# Config_Interfaces.net
KiCad netlist of a schematic drawn in Altium Designer
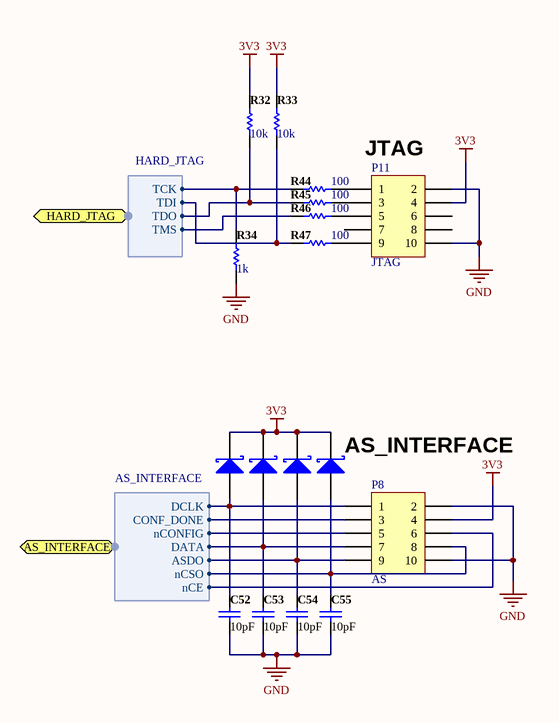
[diagram p0: Config_Interfaces.SchDoc]

(export (version "E")
  (design (tool "Eeschema 10.0.6"))
  (components
    (comp (ref "C52")
      (value "10pF")
      (footprint "0805C-GENERIC")
      (description "Capacitor, Ceramic, 10% 10V 0805 X7R")
      (fields (field (name "CAPACITANCE") "10pF") (field (name "TOLERANCE") "10 %"))
      (libsource (lib "altium-import") (part "root_0_CAP-NP_"))
    )
    (comp (ref "C53")
      (value "10pF")
      (footprint "0805C-GENERIC")
      (description "Capacitor, Ceramic, 10% 10V 0805 X7R")
      (fields (field (name "CAPACITANCE") "10pF") (field (name "TOLERANCE") "10 %"))
      (libsource (lib "altium-import") (part "root_0_CAP-NP_"))
    )
    (comp (ref "C54")
      (value "10pF")
      (footprint "0805C-GENERIC")
      (description "Capacitor, Ceramic, 10% 10V 0805 X7R")
      (fields (field (name "CAPACITANCE") "10pF") (field (name "TOLERANCE") "10 %"))
      (libsource (lib "altium-import") (part "root_0_CAP-NP_"))
    )
    (comp (ref "C55")
      (value "10pF")
      (footprint "0805C-GENERIC")
      (description "Capacitor, Ceramic, 10% 10V 0805 X7R")
      (fields (field (name "CAPACITANCE") "10pF") (field (name "TOLERANCE") "10 %"))
      (libsource (lib "altium-import") (part "root_0_CAP-NP_"))
    )
    (comp (ref "D10")
      (value "D Schottky")
      (footprint "LED-0805-K")
      (description "Schottky Diode - SD0805S020S1R0")
      (fields (field (name "PUBLISHER") "Altium Limited"))
      (libsource (lib "Miscellaneous Devices") (part "D Schottky"))
    )
    (comp (ref "D11")
      (value "D Schottky")
      (footprint "LED-0805-K")
      (description "Schottky Diode - SD0805S020S1R0")
      (fields (field (name "PUBLISHER") "Altium Limited"))
      (libsource (lib "Miscellaneous Devices") (part "D Schottky"))
    )
    (comp (ref "D12")
      (value "D Schottky")
      (footprint "LED-0805-K")
      (description "Schottky Diode - SD0805S020S1R0")
      (fields (field (name "PUBLISHER") "Altium Limited"))
      (libsource (lib "Miscellaneous Devices") (part "D Schottky"))
    )
    (comp (ref "D13")
      (value "D Schottky")
      (footprint "LED-0805-K")
      (description "Schottky Diode - SD0805S020S1R0")
      (fields (field (name "PUBLISHER") "Altium Limited"))
      (libsource (lib "Miscellaneous Devices") (part "D Schottky"))
    )
    (comp (ref "P8")
      (value "Header 5X2")
      (footprint "10P_PCB_HEADER_BRD_MNT")
      (description "Header, 5-Pin, Dual row")
      (fields (field (name "PUBLISHER") "Altium Limited"))
      (libsource (lib "Miscellaneous Connectors") (part "Header 5X2"))
    )
    (comp (ref "P11")
      (value "Header 5X2")
      (footprint "10P_PCB_HEADER_BRD_MNT")
      (description "Header, 5-Pin, Dual row")
      (fields (field (name "PUBLISHER") "Altium Limited"))
      (libsource (lib "Miscellaneous Connectors") (part "Header 5X2"))
    )
    (comp (ref "R32")
      (value "10k")
      (footprint "0805R-10K")
      (fields (field (name "TOLERANCE") "1 %"))
      (libsource (lib "AltiumDesignLibrary") (part "RES"))
    )
    (comp (ref "R33")
      (value "10k")
      (footprint "0805R-10K")
      (fields (field (name "TOLERANCE") "1 %"))
      (libsource (lib "AltiumDesignLibrary") (part "RES"))
    )
    (comp (ref "R34")
      (value "1k")
      (footprint "0805R-1K")
      (fields (field (name "TOLERANCE") "1 %"))
      (libsource (lib "AltiumDesignLibrary") (part "RES"))
    )
    (comp (ref "R44")
      (value "100")
      (footprint "0805R-100")
      (fields (field (name "TOLERANCE") "1 %"))
      (libsource (lib "AltiumDesignLibrary") (part "RES"))
    )
    (comp (ref "R45")
      (value "100")
      (footprint "0805R-100")
      (fields (field (name "TOLERANCE") "1 %"))
      (libsource (lib "AltiumDesignLibrary") (part "RES"))
    )
    (comp (ref "R46")
      (value "100")
      (footprint "0805R-100")
      (fields (field (name "TOLERANCE") "1 %"))
      (libsource (lib "AltiumDesignLibrary") (part "RES"))
    )
    (comp (ref "R47")
      (value "100")
      (footprint "0805R-100")
      (fields (field (name "TOLERANCE") "1 %"))
      (libsource (lib "AltiumDesignLibrary") (part "RES"))
    )
  )
  (nets
    (net (code "3") (name "/ASDO") (class "Default")
      (node (ref "C54") (pin "1") (pinfunction "1_1") (pintype "passive"))
      (node (ref "D12") (pin "A") (pinfunction "A_A") (pintype "passive"))
      (node (ref "P8") (pin "9") (pinfunction "9_9") (pintype "passive"))
    )
    (net (code "4") (name "/CONF_DONE") (class "Default")
      (node (ref "P8") (pin "3") (pinfunction "3_3") (pintype "passive"))
    )
    (net (code "5") (name "/DATA") (class "Default")
      (node (ref "C53") (pin "1") (pinfunction "1_1") (pintype "passive"))
      (node (ref "D11") (pin "A") (pinfunction "A_A") (pintype "passive"))
      (node (ref "P8") (pin "7") (pinfunction "7_7") (pintype "passive"))
    )
    (net (code "6") (name "/DCLK") (class "Default")
      (node (ref "C52") (pin "1") (pinfunction "1_1") (pintype "passive"))
      (node (ref "D10") (pin "A") (pinfunction "A_A") (pintype "passive"))
      (node (ref "P8") (pin "1") (pinfunction "1_1") (pintype "passive"))
    )
    (net (code "7") (name "/TCK") (class "Default")
      (node (ref "R34") (pin "1") (pinfunction "1_1") (pintype "passive"))
      (node (ref "R44") (pin "1") (pinfunction "1_1") (pintype "passive"))
    )
    (net (code "8") (name "/TDI") (class "Default")
      (node (ref "R33") (pin "2") (pinfunction "2_2") (pintype "passive"))
      (node (ref "R47") (pin "1") (pinfunction "1_1") (pintype "passive"))
    )
    (net (code "9") (name "/TDO") (class "Default")
      (node (ref "R32") (pin "2") (pinfunction "2_2") (pintype "passive"))
      (node (ref "R45") (pin "1") (pinfunction "1_1") (pintype "passive"))
    )
    (net (code "10") (name "/TMS") (class "Default")
      (node (ref "R46") (pin "1") (pinfunction "1_1") (pintype "passive"))
    )
    (net (code "11") (name "/nCE") (class "Default")
      (node (ref "P8") (pin "6") (pinfunction "6_6") (pintype "passive"))
    )
    (net (code "12") (name "/nCONFIG") (class "Default")
      (node (ref "P8") (pin "5") (pinfunction "5_5") (pintype "passive"))
    )
    (net (code "13") (name "/nCSO") (class "Default")
      (node (ref "C55") (pin "1") (pinfunction "1_1") (pintype "passive"))
      (node (ref "D13") (pin "A") (pinfunction "A_A") (pintype "passive"))
      (node (ref "P8") (pin "8") (pinfunction "8_8") (pintype "passive"))
    )
    (net (code "16") (name "3V3") (class "Default")
      (node (ref "D10") (pin "K") (pinfunction "K_K") (pintype "passive"))
      (node (ref "D11") (pin "K") (pinfunction "K_K") (pintype "passive"))
      (node (ref "D12") (pin "K") (pinfunction "K_K") (pintype "passive"))
      (node (ref "D13") (pin "K") (pinfunction "K_K") (pintype "passive"))
      (node (ref "P11") (pin "4") (pinfunction "4_4") (pintype "passive"))
      (node (ref "P8") (pin "4") (pinfunction "4_4") (pintype "passive"))
      (node (ref "R32") (pin "1") (pinfunction "1_1") (pintype "passive"))
      (node (ref "R33") (pin "1") (pinfunction "1_1") (pintype "passive"))
    )
    (net (code "17") (name "GND") (class "Default")
      (node (ref "C52") (pin "2") (pinfunction "2_2") (pintype "passive"))
      (node (ref "C53") (pin "2") (pinfunction "2_2") (pintype "passive"))
      (node (ref "C54") (pin "2") (pinfunction "2_2") (pintype "passive"))
      (node (ref "C55") (pin "2") (pinfunction "2_2") (pintype "passive"))
      (node (ref "P11") (pin "10") (pinfunction "10_10") (pintype "passive"))
      (node (ref "P11") (pin "2") (pinfunction "2_2") (pintype "passive"))
      (node (ref "P8") (pin "10") (pinfunction "10_10") (pintype "passive"))
      (node (ref "P8") (pin "2") (pinfunction "2_2") (pintype "passive"))
      (node (ref "R34") (pin "2") (pinfunction "2_2") (pintype "passive"))
    )
    (net (code "18") (name "Net-(P11-Pad1)") (class "Default")
      (node (ref "P11") (pin "1") (pinfunction "1_1") (pintype "passive"))
      (node (ref "R44") (pin "2") (pinfunction "2_2") (pintype "passive"))
    )
    (net (code "19") (name "Net-(P11-Pad3)") (class "Default")
      (node (ref "P11") (pin "3") (pinfunction "3_3") (pintype "passive"))
      (node (ref "R45") (pin "2") (pinfunction "2_2") (pintype "passive"))
    )
    (net (code "20") (name "Net-(P11-Pad5)") (class "Default")
      (node (ref "P11") (pin "5") (pinfunction "5_5") (pintype "passive"))
      (node (ref "R46") (pin "2") (pinfunction "2_2") (pintype "passive"))
    )
    (net (code "21") (name "Net-(P11-Pad9)") (class "Default")
      (node (ref "P11") (pin "9") (pinfunction "9_9") (pintype "passive"))
      (node (ref "R47") (pin "2") (pinfunction "2_2") (pintype "passive"))
    )
    (net (code "22") (name "unconnected-(P11-Pad6)") (class "Default")
      (node (ref "P11") (pin "6") (pinfunction "6_6") (pintype "passive"))
    )
    (net (code "23") (name "unconnected-(P11-Pad7)") (class "Default")
      (node (ref "P11") (pin "7") (pinfunction "7_7") (pintype "passive"))
    )
    (net (code "24") (name "unconnected-(P11-Pad8)") (class "Default")
      (node (ref "P11") (pin "8") (pinfunction "8_8") (pintype "passive"))
    )
  )
)
